# MCU.net
KiCad netlist of a schematic drawn in Altium Designer
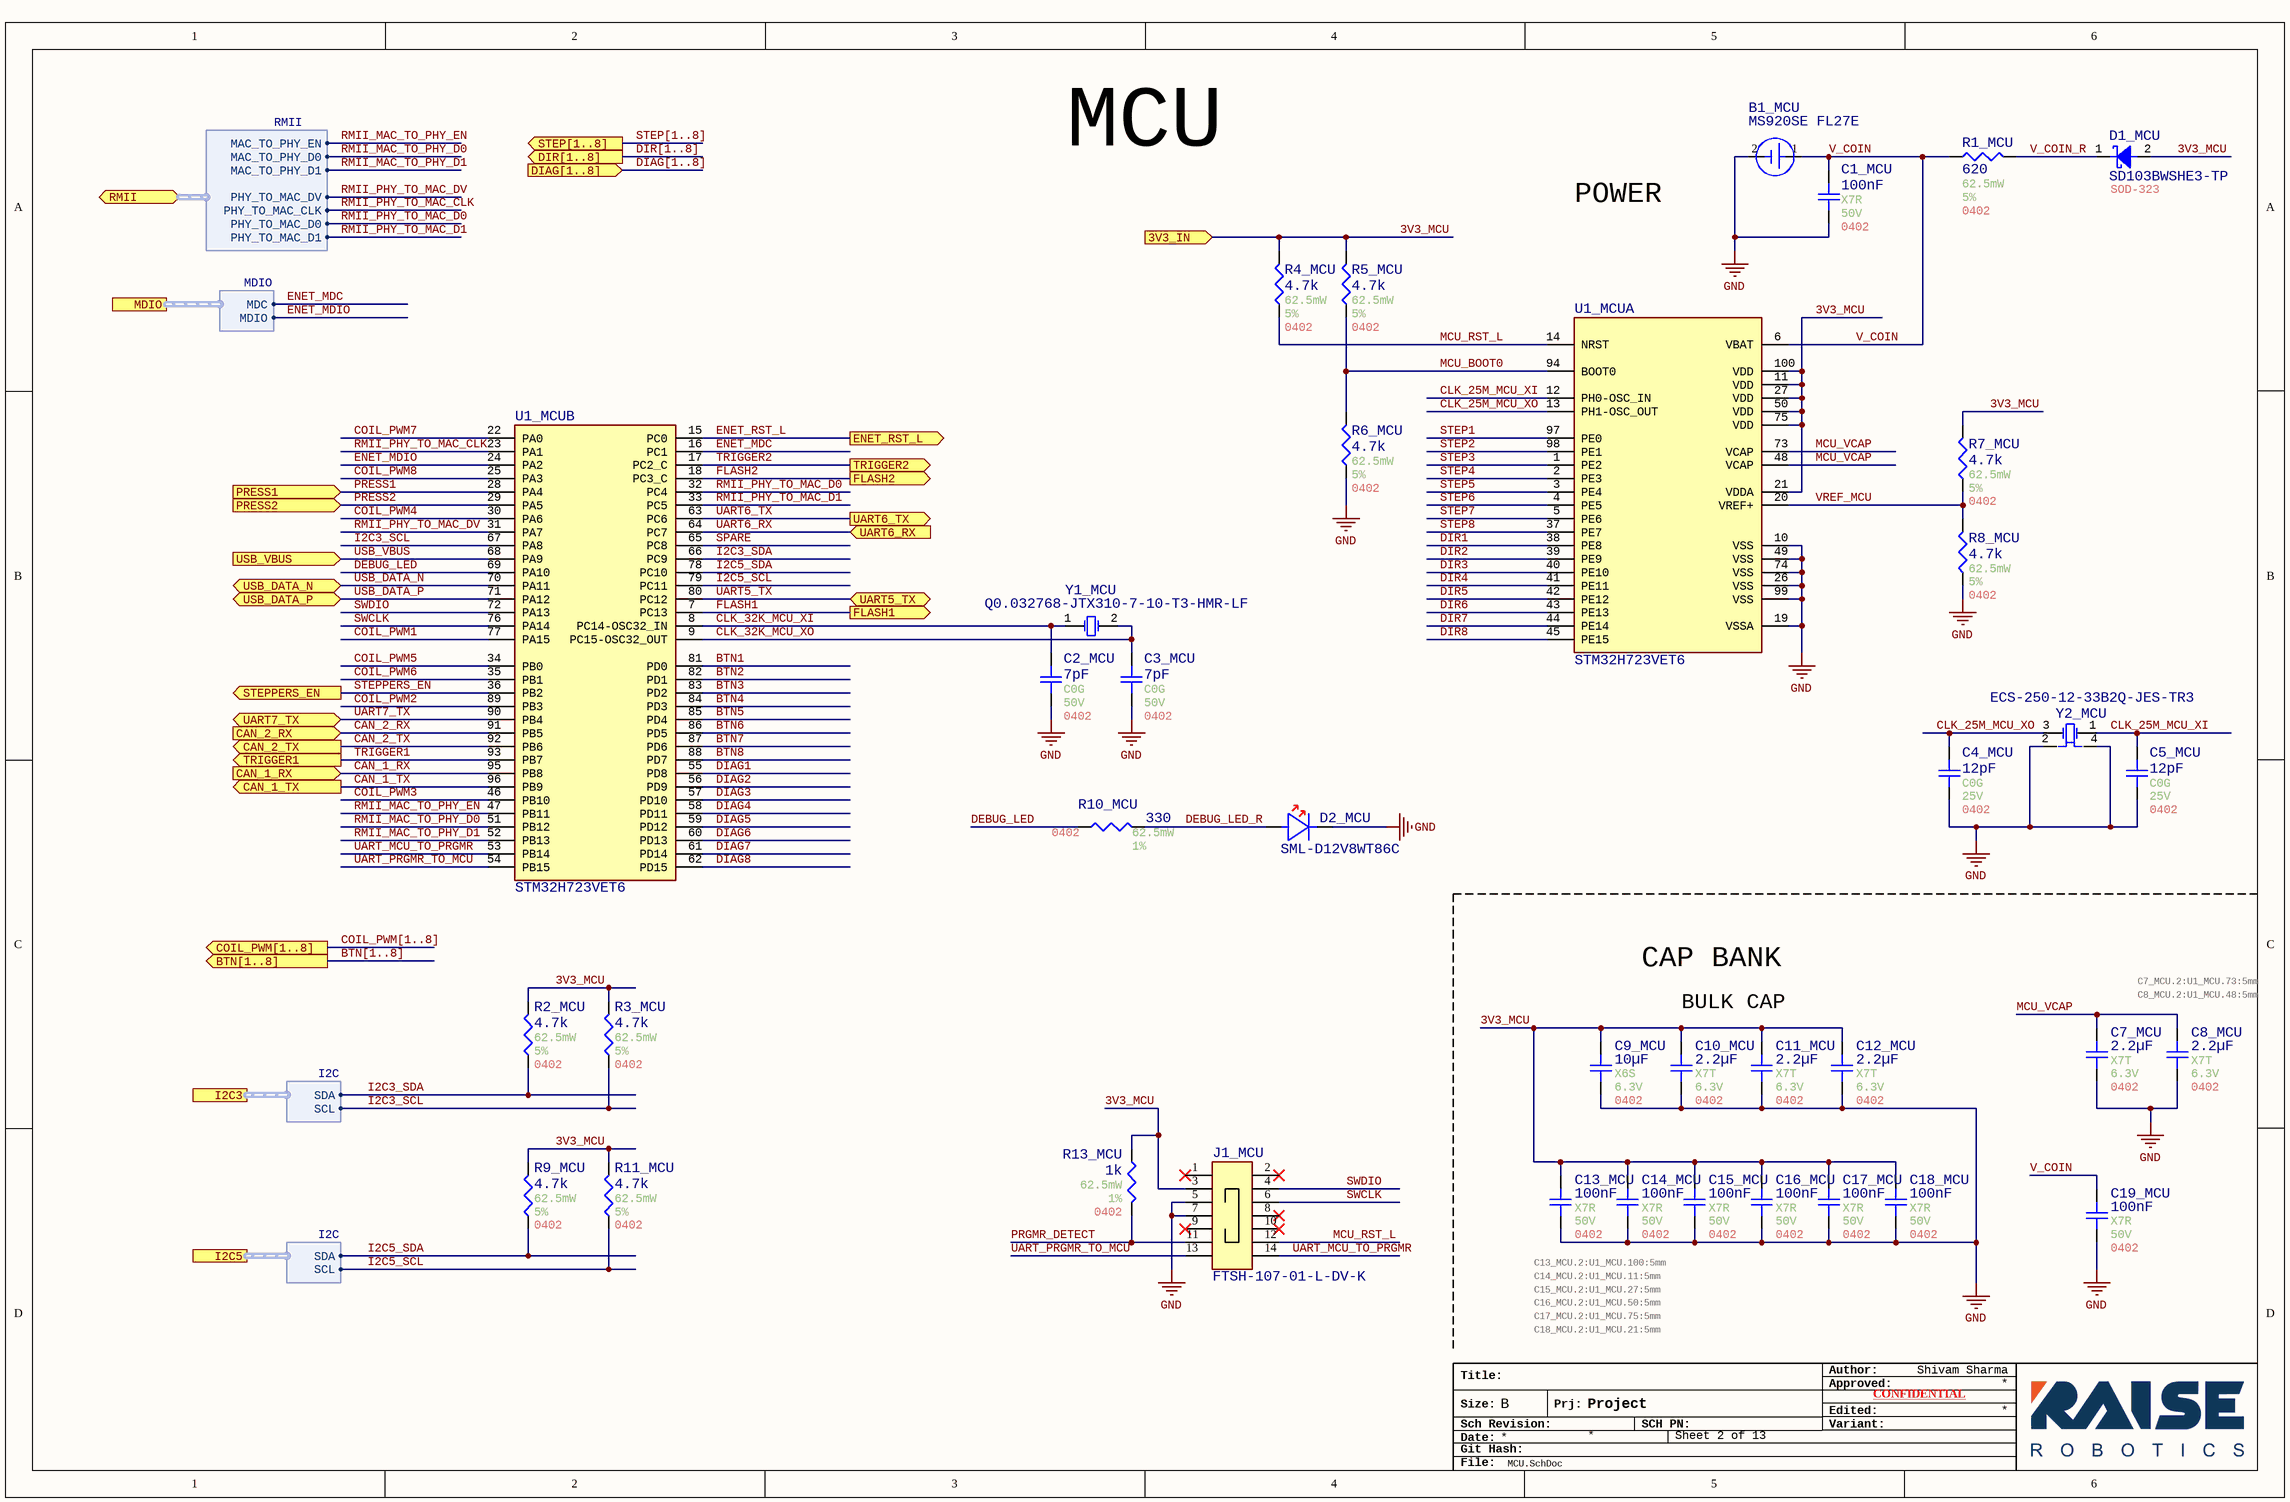
[diagram p0: MCU.SchDoc]

(export (version "E")
  (design (tool "Eeschema 10.0.6"))
  (components
    (comp (ref "B1_MCU")
      (value "MS920SE FL27E")
      (footprint "MS920SE-FL27E")
      (description "Secondary Battery, Manganese Silicon Lithium, 3V, 0.011Ah")
      (libsource (lib "Raise Robotics") (part "Coin Cell"))
    )
    (comp (ref "C1_MCU")
      (value "100nF")
      (footprint "Generic 0402 capacitor")
      (fields
        (field (name "TEMPERATURE COEFFICIENT") "X7R")
        (field (name "VOLTAGE RATING") "50V")
        (field (name "CASE/PACKAGE") "0402")
        (field (name "TOLERANCE") "10%")
        (field (name "Comment") "GRT155R71H104KE01D")
      )
      (libsource (lib "Raise Robotics") (part "Unpolarized Capacitor"))
    )
    (comp (ref "C2_MCU")
      (value "7pF")
      (footprint "Generic 0402 capacitor")
      (fields
        (field (name "TEMPERATURE COEFFICIENT") "C0G")
        (field (name "VOLTAGE RATING") "50V")
        (field (name "CASE/PACKAGE") "0402")
        (field (name "TOLERANCE") "3.5%")
        (field (name "Comment") "GCM1555C1H7R0CA16J")
      )
      (libsource (lib "Raise Robotics") (part "Unpolarized Capacitor"))
    )
    (comp (ref "C3_MCU")
      (value "7pF")
      (footprint "Generic 0402 capacitor")
      (fields
        (field (name "TEMPERATURE COEFFICIENT") "C0G")
        (field (name "VOLTAGE RATING") "50V")
        (field (name "CASE/PACKAGE") "0402")
        (field (name "TOLERANCE") "3.5%")
        (field (name "Comment") "GCM1555C1H7R0CA16J")
      )
      (libsource (lib "Raise Robotics") (part "Unpolarized Capacitor"))
    )
    (comp (ref "C4_MCU")
      (value "12pF")
      (footprint "Generic 0402 capacitor")
      (fields
        (field (name "TEMPERATURE COEFFICIENT") "C0G")
        (field (name "VOLTAGE RATING") "25V")
        (field (name "CASE/PACKAGE") "0402")
        (field (name "TOLERANCE") "5%")
        (field (name "Comment") "GRT1555C1E120JA02J")
      )
      (libsource (lib "Raise Robotics") (part "Unpolarized Capacitor"))
    )
    (comp (ref "C5_MCU")
      (value "12pF")
      (footprint "Generic 0402 capacitor")
      (fields
        (field (name "TEMPERATURE COEFFICIENT") "C0G")
        (field (name "VOLTAGE RATING") "25V")
        (field (name "CASE/PACKAGE") "0402")
        (field (name "TOLERANCE") "5%")
        (field (name "Comment") "GRT1555C1E120JA02J")
      )
      (libsource (lib "Raise Robotics") (part "Unpolarized Capacitor"))
    )
    (comp (ref "C7_MCU")
      (value "2.2µF")
      (footprint "Generic 0402 capacitor")
      (description "Mlcc, 2.2 Uf, # 20 %, 0402, 6.3V, X7T, T&r Q200")
      (fields
        (field (name "TEMPERATURE COEFFICIENT") "X7T")
        (field (name "VOLTAGE RATING") "6.3V")
        (field (name "CASE/PACKAGE") "0402")
        (field (name "TOLERANCE") "20%")
        (field (name "PLACENEAR") "C7_MCU.2:U1_MCU.73:5mm")
        (field (name "Comment") "MAASJ105CD7225MFCA01")
      )
      (libsource (lib "Raise Robotics") (part "Unpolarized Capacitor"))
    )
    (comp (ref "C8_MCU")
      (value "2.2µF")
      (footprint "Generic 0402 capacitor")
      (description "Mlcc, 2.2 Uf, # 20 %, 0402, 6.3V, X7T, T&r Q200")
      (fields
        (field (name "TEMPERATURE COEFFICIENT") "X7T")
        (field (name "VOLTAGE RATING") "6.3V")
        (field (name "CASE/PACKAGE") "0402")
        (field (name "TOLERANCE") "20%")
        (field (name "PLACENEAR") "C8_MCU.2:U1_MCU.48:5mm")
        (field (name "Comment") "MAASJ105CD7225MFCA01")
      )
      (libsource (lib "Raise Robotics") (part "Unpolarized Capacitor"))
    )
    (comp (ref "C9_MCU")
      (value "10µF")
      (footprint "Generic 0402 capacitor")
      (description "Multilayer Ceramic Capacitors MLCC - SMD/SMT 0402 10uF 6.3VDC 20% X6S AEC-Q200")
      (fields
        (field (name "TEMPERATURE COEFFICIENT") "X6S")
        (field (name "VOLTAGE RATING") "6.3V")
        (field (name "CASE/PACKAGE") "0402")
        (field (name "TOLERANCE") "20%")
        (field (name "Comment") "GRT155C80J106ME13J")
      )
      (libsource (lib "Raise Robotics") (part "Unpolarized Capacitor"))
    )
    (comp (ref "C10_MCU")
      (value "2.2µF")
      (footprint "Generic 0402 capacitor")
      (description "Mlcc, 2.2 Uf, # 20 %, 0402, 6.3V, X7T, T&r Q200")
      (fields
        (field (name "TEMPERATURE COEFFICIENT") "X7T")
        (field (name "VOLTAGE RATING") "6.3V")
        (field (name "CASE/PACKAGE") "0402")
        (field (name "TOLERANCE") "20%")
        (field (name "Comment") "MAASJ105CD7225MFCA01")
      )
      (libsource (lib "Raise Robotics") (part "Unpolarized Capacitor"))
    )
    (comp (ref "C11_MCU")
      (value "2.2µF")
      (footprint "Generic 0402 capacitor")
      (description "Mlcc, 2.2 Uf, # 20 %, 0402, 6.3V, X7T, T&r Q200")
      (fields
        (field (name "TEMPERATURE COEFFICIENT") "X7T")
        (field (name "VOLTAGE RATING") "6.3V")
        (field (name "CASE/PACKAGE") "0402")
        (field (name "TOLERANCE") "20%")
        (field (name "Comment") "MAASJ105CD7225MFCA01")
      )
      (libsource (lib "Raise Robotics") (part "Unpolarized Capacitor"))
    )
    (comp (ref "C12_MCU")
      (value "2.2µF")
      (footprint "Generic 0402 capacitor")
      (description "Mlcc, 2.2 Uf, # 20 %, 0402, 6.3V, X7T, T&r Q200")
      (fields
        (field (name "TEMPERATURE COEFFICIENT") "X7T")
        (field (name "VOLTAGE RATING") "6.3V")
        (field (name "CASE/PACKAGE") "0402")
        (field (name "TOLERANCE") "20%")
        (field (name "Comment") "MAASJ105CD7225MFCA01")
      )
      (libsource (lib "Raise Robotics") (part "Unpolarized Capacitor"))
    )
    (comp (ref "C13_MCU")
      (value "100nF")
      (footprint "Generic 0402 capacitor")
      (fields
        (field (name "TEMPERATURE COEFFICIENT") "X7R")
        (field (name "VOLTAGE RATING") "50V")
        (field (name "CASE/PACKAGE") "0402")
        (field (name "TOLERANCE") "10%")
        (field (name "PLACENEAR") "C13_MCU.2:U1_MCU.100:5mm")
        (field (name "Comment") "GRT155R71H104KE01D")
      )
      (libsource (lib "Raise Robotics") (part "Unpolarized Capacitor"))
    )
    (comp (ref "C14_MCU")
      (value "100nF")
      (footprint "Generic 0402 capacitor")
      (fields
        (field (name "TEMPERATURE COEFFICIENT") "X7R")
        (field (name "VOLTAGE RATING") "50V")
        (field (name "CASE/PACKAGE") "0402")
        (field (name "TOLERANCE") "10%")
        (field (name "PLACENEAR") "C14_MCU.2:U1_MCU.11:5mm")
        (field (name "Comment") "GRT155R71H104KE01D")
      )
      (libsource (lib "Raise Robotics") (part "Unpolarized Capacitor"))
    )
    (comp (ref "C15_MCU")
      (value "100nF")
      (footprint "Generic 0402 capacitor")
      (fields
        (field (name "TEMPERATURE COEFFICIENT") "X7R")
        (field (name "VOLTAGE RATING") "50V")
        (field (name "CASE/PACKAGE") "0402")
        (field (name "TOLERANCE") "10%")
        (field (name "PLACENEAR") "C15_MCU.2:U1_MCU.27:5mm")
        (field (name "Comment") "GRT155R71H104KE01D")
      )
      (libsource (lib "Raise Robotics") (part "Unpolarized Capacitor"))
    )
    (comp (ref "C16_MCU")
      (value "100nF")
      (footprint "Generic 0402 capacitor")
      (fields
        (field (name "TEMPERATURE COEFFICIENT") "X7R")
        (field (name "VOLTAGE RATING") "50V")
        (field (name "CASE/PACKAGE") "0402")
        (field (name "TOLERANCE") "10%")
        (field (name "PLACENEAR") "C16_MCU.2:U1_MCU.50:5mm")
        (field (name "Comment") "GRT155R71H104KE01D")
      )
      (libsource (lib "Raise Robotics") (part "Unpolarized Capacitor"))
    )
    (comp (ref "C17_MCU")
      (value "100nF")
      (footprint "Generic 0402 capacitor")
      (fields
        (field (name "TEMPERATURE COEFFICIENT") "X7R")
        (field (name "VOLTAGE RATING") "50V")
        (field (name "CASE/PACKAGE") "0402")
        (field (name "TOLERANCE") "10%")
        (field (name "PLACENEAR") "C17_MCU.2:U1_MCU.75:5mm")
        (field (name "Comment") "GRT155R71H104KE01D")
      )
      (libsource (lib "Raise Robotics") (part "Unpolarized Capacitor"))
    )
    (comp (ref "C18_MCU")
      (value "100nF")
      (footprint "Generic 0402 capacitor")
      (fields
        (field (name "TEMPERATURE COEFFICIENT") "X7R")
        (field (name "VOLTAGE RATING") "50V")
        (field (name "CASE/PACKAGE") "0402")
        (field (name "TOLERANCE") "10%")
        (field (name "PLACENEAR") "C18_MCU.2:U1_MCU.21:5mm")
        (field (name "Comment") "GRT155R71H104KE01D")
      )
      (libsource (lib "Raise Robotics") (part "Unpolarized Capacitor"))
    )
    (comp (ref "C19_MCU")
      (value "100nF")
      (footprint "Generic 0402 capacitor")
      (fields
        (field (name "TEMPERATURE COEFFICIENT") "X7R")
        (field (name "VOLTAGE RATING") "50V")
        (field (name "CASE/PACKAGE") "0402")
        (field (name "TOLERANCE") "10%")
        (field (name "Comment") "GRT155R71H104KE01D")
      )
      (libsource (lib "Raise Robotics") (part "Unpolarized Capacitor"))
    )
    (comp (ref "D1_MCU")
      (value "SD103BWSHE3-TP")
      (footprint "SOD-323")
      (description "Rectifier Diode, Schottky, 1 Phase, 1 Element, 0.35A, 30V V(RRM), Silicon")
      (fields (field (name "CASE/PACKAGE") "SOD-323"))
      (libsource (lib "Raise Robotics") (part "Generic 2 pin Diode"))
    )
    (comp (ref "D2_MCU")
      (value "SML-D12V8WT86C")
      (footprint "FP-SML-D12-MFG")
      (description "Red 630nm LED Indication - Discrete 2.2V 0603 (1608 Metric)")
      (libsource (lib "Raise Robotics") (part "LED Red"))
    )
    (comp (ref "J1_MCU")
      (value "FTSH-107-01-L-DV-K")
      (footprint "FTSH-107-01-L-DV-K-TR")
      (fields (field (name "MANUFACTURER") "Samtec"))
      (libsource (lib "Raise Robotics") (part "FTSH-107-01-L-DV-K-A"))
    )
    (comp (ref "R1_MCU")
      (value "620")
      (footprint "Generic 0402 Resistor")
      (fields
        (field (name "POWER") "62.5mW")
        (field (name "TOLERANCE") "5%")
        (field (name "CASE/PACKAGE") "0402")
        (field (name "Comment") "RC0402JR-07620RL")
      )
      (libsource (lib "Raise Robotics") (part "Resistor"))
    )
    (comp (ref "R2_MCU")
      (value "4.7k")
      (footprint "Generic 0402 Resistor")
      (fields
        (field (name "POWER") "62.5mW")
        (field (name "TOLERANCE") "5%")
        (field (name "CASE/PACKAGE") "0402")
        (field (name "MANUFACTURER PART NUMBER") "Blank")
        (field (name "Comment") "WR04X472JTL")
      )
      (libsource (lib "Raise Robotics") (part "Resistor"))
    )
    (comp (ref "R3_MCU")
      (value "4.7k")
      (footprint "Generic 0402 Resistor")
      (fields
        (field (name "POWER") "62.5mW")
        (field (name "TOLERANCE") "5%")
        (field (name "CASE/PACKAGE") "0402")
        (field (name "MANUFACTURER PART NUMBER") "Blank")
        (field (name "Comment") "WR04X472JTL")
      )
      (libsource (lib "Raise Robotics") (part "Resistor"))
    )
    (comp (ref "R4_MCU")
      (value "4.7k")
      (footprint "Generic 0402 Resistor")
      (fields
        (field (name "POWER") "62.5mW")
        (field (name "TOLERANCE") "5%")
        (field (name "CASE/PACKAGE") "0402")
        (field (name "MANUFACTURER PART NUMBER") "Blank")
        (field (name "Comment") "WR04X472JTL")
      )
      (libsource (lib "Raise Robotics") (part "Resistor"))
    )
    (comp (ref "R5_MCU")
      (value "4.7k")
      (footprint "Generic 0402 Resistor")
      (fields
        (field (name "POWER") "62.5mW")
        (field (name "TOLERANCE") "5%")
        (field (name "CASE/PACKAGE") "0402")
        (field (name "MANUFACTURER PART NUMBER") "Blank")
        (field (name "Comment") "WR04X472JTL")
      )
      (libsource (lib "Raise Robotics") (part "Resistor"))
    )
    (comp (ref "R6_MCU")
      (value "4.7k")
      (footprint "Generic 0402 Resistor")
      (fields
        (field (name "POWER") "62.5mW")
        (field (name "TOLERANCE") "5%")
        (field (name "CASE/PACKAGE") "0402")
        (field (name "MANUFACTURER PART NUMBER") "Blank")
        (field (name "Comment") "WR04X472JTL")
      )
      (libsource (lib "Raise Robotics") (part "Resistor"))
    )
    (comp (ref "R7_MCU")
      (value "4.7k")
      (footprint "Generic 0402 Resistor")
      (fields
        (field (name "POWER") "62.5mW")
        (field (name "TOLERANCE") "5%")
        (field (name "CASE/PACKAGE") "0402")
        (field (name "MANUFACTURER PART NUMBER") "Blank")
        (field (name "Comment") "WR04X472JTL")
      )
      (libsource (lib "Raise Robotics") (part "Resistor"))
    )
    (comp (ref "R8_MCU")
      (value "4.7k")
      (footprint "Generic 0402 Resistor")
      (fields
        (field (name "POWER") "62.5mW")
        (field (name "TOLERANCE") "5%")
        (field (name "CASE/PACKAGE") "0402")
        (field (name "MANUFACTURER PART NUMBER") "Blank")
        (field (name "Comment") "WR04X472JTL")
      )
      (libsource (lib "Raise Robotics") (part "Resistor"))
    )
    (comp (ref "R9_MCU")
      (value "4.7k")
      (footprint "Generic 0402 Resistor")
      (fields
        (field (name "POWER") "62.5mW")
        (field (name "TOLERANCE") "5%")
        (field (name "CASE/PACKAGE") "0402")
        (field (name "MANUFACTURER PART NUMBER") "Blank")
        (field (name "Comment") "WR04X472JTL")
      )
      (libsource (lib "Raise Robotics") (part "Resistor"))
    )
    (comp (ref "R10_MCU")
      (value "330")
      (footprint "Generic 0402 Resistor")
      (description "Res Thick Film 0402 330 Ohm 1% 0.063W ±100ppm/°C Molded SMD Paper T/R")
      (fields
        (field (name "POWER") "62.5mW")
        (field (name "TOLERANCE") "1%")
        (field (name "CASE/PACKAGE") "0402")
        (field (name "Comment") "RMCF0402FT330R")
      )
      (libsource (lib "Raise Robotics") (part "Resistor"))
    )
    (comp (ref "R11_MCU")
      (value "4.7k")
      (footprint "Generic 0402 Resistor")
      (fields
        (field (name "POWER") "62.5mW")
        (field (name "TOLERANCE") "5%")
        (field (name "CASE/PACKAGE") "0402")
        (field (name "MANUFACTURER PART NUMBER") "Blank")
        (field (name "Comment") "WR04X472JTL")
      )
      (libsource (lib "Raise Robotics") (part "Resistor"))
    )
    (comp (ref "R13_MCU")
      (value "1k")
      (footprint "Generic 0402 Resistor")
      (fields
        (field (name "POWER") "62.5mW")
        (field (name "TOLERANCE") "1%")
        (field (name "CASE/PACKAGE") "0402")
        (field (name "MANUFACTURER PART NUMBER") "Blank")
        (field (name "Comment") "WR04X1001FTL")
      )
      (libsource (lib "Raise Robotics") (part "Resistor"))
    )
    (comp (ref "U1_MCU")
      (value "STM32H723VET6")
      (footprint "STM32H723VxT")
      (description "MCU 32-bit ARM Cortex M7 RISC 512KB Flash 1.8V/2.5V/3.3V 100-Pin LQFP Tray")
      (libsource (lib "Raise Robotics") (part "STM32H723VET6"))
    )
    (comp (ref "Y1_MCU")
      (value "Q0.032768-JTX310-7-10-T3-HMR-LF")
      (footprint "JTX310")
      (description "Parallel - Fundamental Quartz Crystal, 0.032768MHz Nom")
      (libsource (lib "Raise Robotics") (part "XTAL-2"))
    )
    (comp (ref "Y2_MCU")
      (value "ECS-250-12-33B2Q-JES-TR3")
      (footprint "ECS-250-12-33B2Q-JES-TR3")
      (description "Crystal 25.000 Mhz 12PF SMD")
      (libsource (lib "") (part "XTAL-2_1"))
    )
  )
  (nets
    (net (code "4") (name "/3V3_MCU") (class "Default")
      (node (ref "C10_MCU") (pin "2") (pinfunction "2_2") (pintype "passive"))
      (node (ref "C11_MCU") (pin "2") (pinfunction "2_2") (pintype "passive"))
      (node (ref "C12_MCU") (pin "2") (pinfunction "2_2") (pintype "passive"))
      (node (ref "C13_MCU") (pin "2") (pinfunction "2_2") (pintype "passive"))
      (node (ref "C14_MCU") (pin "2") (pinfunction "2_2") (pintype "passive"))
      (node (ref "C15_MCU") (pin "2") (pinfunction "2_2") (pintype "passive"))
      (node (ref "C16_MCU") (pin "2") (pinfunction "2_2") (pintype "passive"))
      (node (ref "C17_MCU") (pin "2") (pinfunction "2_2") (pintype "passive"))
      (node (ref "C18_MCU") (pin "2") (pinfunction "2_2") (pintype "passive"))
      (node (ref "C9_MCU") (pin "2") (pinfunction "2_2") (pintype "passive"))
      (node (ref "D1_MCU") (pin "2") (pinfunction "A_2") (pintype "passive"))
      (node (ref "J1_MCU") (pin "3") (pinfunction "3_3") (pintype "passive"))
      (node (ref "R11_MCU") (pin "2") (pinfunction "2_2") (pintype "passive"))
      (node (ref "R13_MCU") (pin "2") (pinfunction "2_2") (pintype "passive"))
      (node (ref "R2_MCU") (pin "2") (pinfunction "2_2") (pintype "passive"))
      (node (ref "R3_MCU") (pin "2") (pinfunction "2_2") (pintype "passive"))
      (node (ref "R4_MCU") (pin "2") (pinfunction "2_2") (pintype "passive"))
      (node (ref "R5_MCU") (pin "2") (pinfunction "2_2") (pintype "passive"))
      (node (ref "R7_MCU") (pin "2") (pinfunction "2_2") (pintype "passive"))
      (node (ref "R9_MCU") (pin "2") (pinfunction "2_2") (pintype "passive"))
      (node (ref "U1_MCU") (pin "100") (pinfunction "VDD_100") (pintype "passive"))
      (node (ref "U1_MCU") (pin "11") (pinfunction "VDD_11") (pintype "passive"))
      (node (ref "U1_MCU") (pin "21") (pinfunction "VDDA_21") (pintype "passive"))
      (node (ref "U1_MCU") (pin "27") (pinfunction "VDD_27") (pintype "passive"))
      (node (ref "U1_MCU") (pin "50") (pinfunction "VDD_50") (pintype "passive"))
      (node (ref "U1_MCU") (pin "75") (pinfunction "VDD_75") (pintype "passive"))
    )
    (net (code "5") (name "/BTN1") (class "Default")
      (node (ref "U1_MCU") (pin "81") (pinfunction "PD0_81") (pintype "passive"))
    )
    (net (code "6") (name "/BTN2") (class "Default")
      (node (ref "U1_MCU") (pin "82") (pinfunction "PD1_82") (pintype "passive"))
    )
    (net (code "7") (name "/BTN3") (class "Default")
      (node (ref "U1_MCU") (pin "83") (pinfunction "PD2_83") (pintype "passive"))
    )
    (net (code "8") (name "/BTN4") (class "Default")
      (node (ref "U1_MCU") (pin "84") (pinfunction "PD3_84") (pintype "passive"))
    )
    (net (code "9") (name "/BTN5") (class "Default")
      (node (ref "U1_MCU") (pin "85") (pinfunction "PD4_85") (pintype "passive"))
    )
    (net (code "10") (name "/BTN6") (class "Default")
      (node (ref "U1_MCU") (pin "86") (pinfunction "PD5_86") (pintype "passive"))
    )
    (net (code "11") (name "/BTN7") (class "Default")
      (node (ref "U1_MCU") (pin "87") (pinfunction "PD6_87") (pintype "passive"))
    )
    (net (code "12") (name "/BTN8") (class "Default")
      (node (ref "U1_MCU") (pin "88") (pinfunction "PD7_88") (pintype "passive"))
    )
    (net (code "14") (name "/CAN_1_RX") (class "Default")
      (node (ref "U1_MCU") (pin "95") (pinfunction "PB8_95") (pintype "passive"))
    )
    (net (code "15") (name "/CAN_1_TX") (class "Default")
      (node (ref "U1_MCU") (pin "96") (pinfunction "PB9_96") (pintype "passive"))
    )
    (net (code "16") (name "/CAN_2_RX") (class "Default")
      (node (ref "U1_MCU") (pin "91") (pinfunction "PB5_91") (pintype "passive"))
    )
    (net (code "17") (name "/CAN_2_TX") (class "Default")
      (node (ref "U1_MCU") (pin "92") (pinfunction "PB6_92") (pintype "passive"))
    )
    (net (code "18") (name "/CLK_25M_MCU_XI") (class "Default")
      (node (ref "C5_MCU") (pin "2") (pinfunction "2_2") (pintype "passive"))
      (node (ref "U1_MCU") (pin "12") (pinfunction "PH0-OSC_IN_12") (pintype "passive"))
      (node (ref "Y2_MCU") (pin "1") (pinfunction "1_1") (pintype "passive"))
    )
    (net (code "19") (name "/CLK_25M_MCU_XO") (class "Default")
      (node (ref "C4_MCU") (pin "2") (pinfunction "2_2") (pintype "passive"))
      (node (ref "U1_MCU") (pin "13") (pinfunction "PH1-OSC_OUT_13") (pintype "passive"))
      (node (ref "Y2_MCU") (pin "3") (pinfunction "3_3") (pintype "passive"))
    )
    (net (code "20") (name "/CLK_32K_MCU_XI") (class "Default")
      (node (ref "C2_MCU") (pin "2") (pinfunction "2_2") (pintype "passive"))
      (node (ref "U1_MCU") (pin "8") (pinfunction "PC14-OSC32_IN_8") (pintype "passive"))
      (node (ref "Y1_MCU") (pin "1") (pinfunction "1_1") (pintype "passive"))
    )
    (net (code "21") (name "/CLK_32K_MCU_XO") (class "Default")
      (node (ref "C3_MCU") (pin "2") (pinfunction "2_2") (pintype "passive"))
      (node (ref "U1_MCU") (pin "9") (pinfunction "PC15-OSC32_OUT_9") (pintype "passive"))
      (node (ref "Y1_MCU") (pin "2") (pinfunction "2_2") (pintype "passive"))
    )
    (net (code "22") (name "/COIL_PWM1") (class "Default")
      (node (ref "U1_MCU") (pin "77") (pinfunction "PA15_77") (pintype "passive"))
    )
    (net (code "23") (name "/COIL_PWM2") (class "Default")
      (node (ref "U1_MCU") (pin "89") (pinfunction "PB3_89") (pintype "passive"))
    )
    (net (code "24") (name "/COIL_PWM3") (class "Default")
      (node (ref "U1_MCU") (pin "46") (pinfunction "PB10_46") (pintype "passive"))
    )
    (net (code "25") (name "/COIL_PWM4") (class "Default")
      (node (ref "U1_MCU") (pin "30") (pinfunction "PA6_30") (pintype "passive"))
    )
    (net (code "26") (name "/COIL_PWM5") (class "Default")
      (node (ref "U1_MCU") (pin "34") (pinfunction "PB0_34") (pintype "passive"))
    )
    (net (code "27") (name "/COIL_PWM6") (class "Default")
      (node (ref "U1_MCU") (pin "35") (pinfunction "PB1_35") (pintype "passive"))
    )
    (net (code "28") (name "/COIL_PWM7") (class "Default")
      (node (ref "U1_MCU") (pin "22") (pinfunction "PA0_22") (pintype "passive"))
    )
    (net (code "29") (name "/COIL_PWM8") (class "Default")
      (node (ref "U1_MCU") (pin "25") (pinfunction "PA3_25") (pintype "passive"))
    )
    (net (code "31") (name "/DEBUG_LED") (class "Default")
      (node (ref "R10_MCU") (pin "1") (pinfunction "1_1") (pintype "passive"))
      (node (ref "U1_MCU") (pin "69") (pinfunction "PA10_69") (pintype "passive"))
    )
    (net (code "32") (name "/DEBUG_LED_R") (class "Default")
      (node (ref "D2_MCU") (pin "2") (pinfunction "A_2") (pintype "passive"))
      (node (ref "R10_MCU") (pin "2") (pinfunction "2_2") (pintype "passive"))
    )
    (net (code "33") (name "/DIAG1") (class "Default")
      (node (ref "U1_MCU") (pin "55") (pinfunction "PD8_55") (pintype "passive"))
    )
    (net (code "34") (name "/DIAG2") (class "Default")
      (node (ref "U1_MCU") (pin "56") (pinfunction "PD9_56") (pintype "passive"))
    )
    (net (code "35") (name "/DIAG3") (class "Default")
      (node (ref "U1_MCU") (pin "57") (pinfunction "PD10_57") (pintype "passive"))
    )
    (net (code "36") (name "/DIAG4") (class "Default")
      (node (ref "U1_MCU") (pin "58") (pinfunction "PD11_58") (pintype "passive"))
    )
    (net (code "37") (name "/DIAG5") (class "Default")
      (node (ref "U1_MCU") (pin "59") (pinfunction "PD12_59") (pintype "passive"))
    )
    (net (code "38") (name "/DIAG6") (class "Default")
      (node (ref "U1_MCU") (pin "60") (pinfunction "PD13_60") (pintype "passive"))
    )
    (net (code "39") (name "/DIAG7") (class "Default")
      (node (ref "U1_MCU") (pin "61") (pinfunction "PD14_61") (pintype "passive"))
    )
    (net (code "40") (name "/DIAG8") (class "Default")
      (node (ref "U1_MCU") (pin "62") (pinfunction "PD15_62") (pintype "passive"))
    )
    (net (code "42") (name "/DIR1") (class "Default")
      (node (ref "U1_MCU") (pin "38") (pinfunction "PE8_38") (pintype "passive"))
    )
    (net (code "43") (name "/DIR2") (class "Default")
      (node (ref "U1_MCU") (pin "39") (pinfunction "PE9_39") (pintype "passive"))
    )
    (net (code "44") (name "/DIR3") (class "Default")
      (node (ref "U1_MCU") (pin "40") (pinfunction "PE10_40") (pintype "passive"))
    )
    (net (code "45") (name "/DIR4") (class "Default")
      (node (ref "U1_MCU") (pin "41") (pinfunction "PE11_41") (pintype "passive"))
    )
    (net (code "46") (name "/DIR5") (class "Default")
      (node (ref "U1_MCU") (pin "42") (pinfunction "PE12_42") (pintype "passive"))
    )
    (net (code "47") (name "/DIR6") (class "Default")
      (node (ref "U1_MCU") (pin "43") (pinfunction "PE13_43") (pintype "passive"))
    )
    (net (code "48") (name "/DIR7") (class "Default")
      (node (ref "U1_MCU") (pin "44") (pinfunction "PE14_44") (pintype "passive"))
    )
    (net (code "49") (name "/DIR8") (class "Default")
      (node (ref "U1_MCU") (pin "45") (pinfunction "PE15_45") (pintype "passive"))
    )
    (net (code "51") (name "/ENET_MDC") (class "Default")
      (node (ref "U1_MCU") (pin "16") (pinfunction "PC1_16") (pintype "passive"))
    )
    (net (code "52") (name "/ENET_MDIO") (class "Default")
      (node (ref "U1_MCU") (pin "24") (pinfunction "PA2_24") (pintype "passive"))
    )
    (net (code "53") (name "/ENET_RST_L") (class "Default")
      (node (ref "U1_MCU") (pin "15") (pinfunction "PC0_15") (pintype "passive"))
    )
    (net (code "54") (name "/FLASH1") (class "Default")
      (node (ref "U1_MCU") (pin "7") (pinfunction "PC13_7") (pintype "passive"))
    )
    (net (code "55") (name "/FLASH2") (class "Default")
      (node (ref "U1_MCU") (pin "18") (pinfunction "PC3_C_18") (pintype "passive"))
    )
    (net (code "56") (name "/I2C3_SCL") (class "Default")
      (node (ref "R3_MCU") (pin "1") (pinfunction "1_1") (pintype "passive"))
      (node (ref "U1_MCU") (pin "67") (pinfunction "PA8_67") (pintype "passive"))
    )
    (net (code "57") (name "/I2C3_SDA") (class "Default")
      (node (ref "R2_MCU") (pin "1") (pinfunction "1_1") (pintype "passive"))
      (node (ref "U1_MCU") (pin "66") (pinfunction "PC9_66") (pintype "passive"))
    )
    (net (code "58") (name "/I2C5_SCL") (class "Default")
      (node (ref "R11_MCU") (pin "1") (pinfunction "1_1") (pintype "passive"))
      (node (ref "U1_MCU") (pin "79") (pinfunction "PC11_79") (pintype "passive"))
    )
    (net (code "59") (name "/I2C5_SDA") (class "Default")
      (node (ref "R9_MCU") (pin "1") (pinfunction "1_1") (pintype "passive"))
      (node (ref "U1_MCU") (pin "78") (pinfunction "PC10_78") (pintype "passive"))
    )
    (net (code "60") (name "/MCU_BOOT0") (class "Default")
      (node (ref "R5_MCU") (pin "1") (pinfunction "1_1") (pintype "passive"))
      (node (ref "R6_MCU") (pin "2") (pinfunction "2_2") (pintype "passive"))
      (node (ref "U1_MCU") (pin "94") (pinfunction "BOOT0_94") (pintype "passive"))
    )
    (net (code "61") (name "/MCU_RST_L") (class "Default")
      (node (ref "J1_MCU") (pin "12") (pinfunction "12_12") (pintype "passive"))
      (node (ref "R4_MCU") (pin "1") (pinfunction "1_1") (pintype "passive"))
      (node (ref "U1_MCU") (pin "14") (pinfunction "NRST_14") (pintype "passive"))
    )
    (net (code "62") (name "/MCU_VCAP") (class "Default")
      (node (ref "C7_MCU") (pin "2") (pinfunction "2_2") (pintype "passive"))
      (node (ref "C8_MCU") (pin "2") (pinfunction "2_2") (pintype "passive"))
      (node (ref "U1_MCU") (pin "48") (pinfunction "VCAP_48") (pintype "passive"))
      (node (ref "U1_MCU") (pin "73") (pinfunction "VCAP_73") (pintype "passive"))
    )
    (net (code "63") (name "/PRESS1") (class "Default")
      (node (ref "U1_MCU") (pin "28") (pinfunction "PA4_28") (pintype "passive"))
    )
    (net (code "64") (name "/PRESS2") (class "Default")
      (node (ref "U1_MCU") (pin "29") (pinfunction "PA5_29") (pintype "passive"))
    )
    (net (code "65") (name "/PRGMR_DETECT") (class "Default")
      (node (ref "J1_MCU") (pin "11") (pinfunction "11_11") (pintype "passive"))
      (node (ref "R13_MCU") (pin "1") (pinfunction "1_1") (pintype "passive"))
    )
    (net (code "66") (name "/RMII_MAC_TO_PHY_D0") (class "Default")
      (node (ref "U1_MCU") (pin "51") (pinfunction "PB12_51") (pintype "passive"))
    )
    (net (code "67") (name "/RMII_MAC_TO_PHY_D1") (class "Default")
      (node (ref "U1_MCU") (pin "52") (pinfunction "PB13_52") (pintype "passive"))
    )
    (net (code "68") (name "/RMII_MAC_TO_PHY_EN") (class "Default")
      (node (ref "U1_MCU") (pin "47") (pinfunction "PB11_47") (pintype "passive"))
    )
    (net (code "69") (name "/RMII_PHY_TO_MAC_CLK") (class "Default")
      (node (ref "U1_MCU") (pin "23") (pinfunction "PA1_23") (pintype "passive"))
    )
    (net (code "70") (name "/RMII_PHY_TO_MAC_D0") (class "Default")
      (node (ref "U1_MCU") (pin "32") (pinfunction "PC4_32") (pintype "passive"))
    )
    (net (code "71") (name "/RMII_PHY_TO_MAC_D1") (class "Default")
      (node (ref "U1_MCU") (pin "33") (pinfunction "PC5_33") (pintype "passive"))
    )
    (net (code "72") (name "/RMII_PHY_TO_MAC_DV") (class "Default")
      (node (ref "U1_MCU") (pin "31") (pinfunction "PA7_31") (pintype "passive"))
    )
    (net (code "73") (name "/SPARE") (class "Default")
      (node (ref "U1_MCU") (pin "65") (pinfunction "PC8_65") (pintype "passive"))
    )
    (net (code "74") (name "/STEP1") (class "Default")
      (node (ref "U1_MCU") (pin "97") (pinfunction "PE0_97") (pintype "passive"))
    )
    (net (code "75") (name "/STEP2") (class "Default")
      (node (ref "U1_MCU") (pin "98") (pinfunction "PE1_98") (pintype "passive"))
    )
    (net (code "76") (name "/STEP3") (class "Default")
      (node (ref "U1_MCU") (pin "1") (pinfunction "PE2_1") (pintype "passive"))
    )
    (net (code "77") (name "/STEP4") (class "Default")
      (node (ref "U1_MCU") (pin "2") (pinfunction "PE3_2") (pintype "passive"))
    )
    (net (code "78") (name "/STEP5") (class "Default")
      (node (ref "U1_MCU") (pin "3") (pinfunction "PE4_3") (pintype "passive"))
    )
    (net (code "79") (name "/STEP6") (class "Default")
      (node (ref "U1_MCU") (pin "4") (pinfunction "PE5_4") (pintype "passive"))
    )
    (net (code "80") (name "/STEP7") (class "Default")
      (node (ref "U1_MCU") (pin "5") (pinfunction "PE6_5") (pintype "passive"))
    )
    (net (code "81") (name "/STEP8") (class "Default")
      (node (ref "U1_MCU") (pin "37") (pinfunction "PE7_37") (pintype "passive"))
    )
    (net (code "82") (name "/STEPPERS_EN") (class "Default")
      (node (ref "U1_MCU") (pin "36") (pinfunction "PB2_36") (pintype "passive"))
    )
    (net (code "84") (name "/SWCLK") (class "Default")
      (node (ref "J1_MCU") (pin "6") (pinfunction "6_6") (pintype "passive"))
      (node (ref "U1_MCU") (pin "76") (pinfunction "PA14_76") (pintype "passive"))
    )
    (net (code "85") (name "/SWDIO") (class "Default")
      (node (ref "J1_MCU") (pin "4") (pinfunction "4_4") (pintype "passive"))
      (node (ref "U1_MCU") (pin "72") (pinfunction "PA13_72") (pintype "passive"))
    )
    (net (code "86") (name "/TRIGGER1") (class "Default")
      (node (ref "U1_MCU") (pin "93") (pinfunction "PB7_93") (pintype "passive"))
    )
    (net (code "87") (name "/TRIGGER2") (class "Default")
      (node (ref "U1_MCU") (pin "17") (pinfunction "PC2_C_17") (pintype "passive"))
    )
    (net (code "88") (name "/UART5_TX") (class "Default")
      (node (ref "U1_MCU") (pin "80") (pinfunction "PC12_80") (pintype "passive"))
    )
    (net (code "89") (name "/UART6_RX") (class "Default")
      (node (ref "U1_MCU") (pin "64") (pinfunction "PC7_64") (pintype "passive"))
    )
    (net (code "90") (name "/UART6_TX") (class "Default")
      (node (ref "U1_MCU") (pin "63") (pinfunction "PC6_63") (pintype "passive"))
    )
    (net (code "91") (name "/UART7_TX") (class "Default")
      (node (ref "U1_MCU") (pin "90") (pinfunction "PB4_90") (pintype "passive"))
    )
    (net (code "92") (name "/UART_MCU_TO_PRGMR") (class "Default")
      (node (ref "J1_MCU") (pin "14") (pinfunction "14_14") (pintype "passive"))
      (node (ref "U1_MCU") (pin "53") (pinfunction "PB14_53") (pintype "passive"))
    )
    (net (code "93") (name "/UART_PRGMR_TO_MCU") (class "Default")
      (node (ref "J1_MCU") (pin "13") (pinfunction "13_13") (pintype "passive"))
      (node (ref "U1_MCU") (pin "54") (pinfunction "PB15_54") (pintype "passive"))
    )
    (net (code "94") (name "/USB_DATA_N") (class "Default")
      (node (ref "U1_MCU") (pin "70") (pinfunction "PA11_70") (pintype "passive"))
    )
    (net (code "95") (name "/USB_DATA_P") (class "Default")
      (node (ref "U1_MCU") (pin "71") (pinfunction "PA12_71") (pintype "passive"))
    )
    (net (code "96") (name "/USB_VBUS") (class "Default")
      (node (ref "U1_MCU") (pin "68") (pinfunction "PA9_68") (pintype "passive"))
    )
    (net (code "97") (name "/VREF_MCU") (class "Default")
      (node (ref "R7_MCU") (pin "1") (pinfunction "1_1") (pintype "passive"))
      (node (ref "R8_MCU") (pin "2") (pinfunction "2_2") (pintype "passive"))
      (node (ref "U1_MCU") (pin "20") (pinfunction "VREF+_20") (pintype "passive"))
    )
    (net (code "98") (name "/V_COIN") (class "Default")
      (node (ref "B1_MCU") (pin "1") (pinfunction "1_1") (pintype "passive"))
      (node (ref "C19_MCU") (pin "2") (pinfunction "2_2") (pintype "passive"))
      (node (ref "C1_MCU") (pin "2") (pinfunction "2_2") (pintype "passive"))
      (node (ref "R1_MCU") (pin "1") (pinfunction "1_1") (pintype "passive"))
      (node (ref "U1_MCU") (pin "6") (pinfunction "VBAT_6") (pintype "passive"))
    )
    (net (code "99") (name "/V_COIN_R") (class "Default")
      (node (ref "D1_MCU") (pin "1") (pinfunction "C_1") (pintype "passive"))
      (node (ref "R1_MCU") (pin "2") (pinfunction "2_2") (pintype "passive"))
    )
    (net (code "103") (name "GND") (class "Default")
      (node (ref "B1_MCU") (pin "2") (pinfunction "2_2") (pintype "passive"))
      (node (ref "C10_MCU") (pin "1") (pinfunction "1_1") (pintype "passive"))
      (node (ref "C11_MCU") (pin "1") (pinfunction "1_1") (pintype "passive"))
      (node (ref "C12_MCU") (pin "1") (pinfunction "1_1") (pintype "passive"))
      (node (ref "C13_MCU") (pin "1") (pinfunction "1_1") (pintype "passive"))
      (node (ref "C14_MCU") (pin "1") (pinfunction "1_1") (pintype "passive"))
      (node (ref "C15_MCU") (pin "1") (pinfunction "1_1") (pintype "passive"))
      (node (ref "C16_MCU") (pin "1") (pinfunction "1_1") (pintype "passive"))
      (node (ref "C17_MCU") (pin "1") (pinfunction "1_1") (pintype "passive"))
      (node (ref "C18_MCU") (pin "1") (pinfunction "1_1") (pintype "passive"))
      (node (ref "C19_MCU") (pin "1") (pinfunction "1_1") (pintype "passive"))
      (node (ref "C1_MCU") (pin "1") (pinfunction "1_1") (pintype "passive"))
      (node (ref "C2_MCU") (pin "1") (pinfunction "1_1") (pintype "passive"))
      (node (ref "C3_MCU") (pin "1") (pinfunction "1_1") (pintype "passive"))
      (node (ref "C4_MCU") (pin "1") (pinfunction "1_1") (pintype "passive"))
      (node (ref "C5_MCU") (pin "1") (pinfunction "1_1") (pintype "passive"))
      (node (ref "C7_MCU") (pin "1") (pinfunction "1_1") (pintype "passive"))
      (node (ref "C8_MCU") (pin "1") (pinfunction "1_1") (pintype "passive"))
      (node (ref "C9_MCU") (pin "1") (pinfunction "1_1") (pintype "passive"))
      (node (ref "D2_MCU") (pin "1") (pinfunction "C_1") (pintype "passive"))
      (node (ref "J1_MCU") (pin "5") (pinfunction "5_5") (pintype "passive"))
      (node (ref "J1_MCU") (pin "7") (pinfunction "7_7") (pintype "passive"))
      (node (ref "R6_MCU") (pin "1") (pinfunction "1_1") (pintype "passive"))
      (node (ref "R8_MCU") (pin "1") (pinfunction "1_1") (pintype "passive"))
      (node (ref "U1_MCU") (pin "10") (pinfunction "VSS_10") (pintype "passive"))
      (node (ref "U1_MCU") (pin "19") (pinfunction "VSSA_19") (pintype "passive"))
      (node (ref "U1_MCU") (pin "26") (pinfunction "VSS_26") (pintype "passive"))
      (node (ref "U1_MCU") (pin "49") (pinfunction "VSS_49") (pintype "passive"))
      (node (ref "U1_MCU") (pin "74") (pinfunction "VSS_74") (pintype "passive"))
      (node (ref "U1_MCU") (pin "99") (pinfunction "VSS_99") (pintype "passive"))
      (node (ref "Y2_MCU") (pin "2") (pinfunction "2_2") (pintype "passive"))
      (node (ref "Y2_MCU") (pin "4") (pinfunction "4_4") (pintype "passive"))
    )
    (net (code "104") (name "unconnected-(J1_MCU-Pad1)") (class "Default")
      (node (ref "J1_MCU") (pin "1") (pinfunction "1_1") (pintype "passive+no_connect"))
    )
    (net (code "105") (name "unconnected-(J1_MCU-Pad2)") (class "Default")
      (node (ref "J1_MCU") (pin "2") (pinfunction "2_2") (pintype "passive+no_connect"))
    )
    (net (code "106") (name "unconnected-(J1_MCU-Pad8)") (class "Default")
      (node (ref "J1_MCU") (pin "8") (pinfunction "8_8") (pintype "passive+no_connect"))
    )
    (net (code "107") (name "unconnected-(J1_MCU-Pad9)") (class "Default")
      (node (ref "J1_MCU") (pin "9") (pinfunction "9_9") (pintype "passive+no_connect"))
    )
    (net (code "108") (name "unconnected-(J1_MCU-Pad10)") (class "Default")
      (node (ref "J1_MCU") (pin "10") (pinfunction "10_10") (pintype "passive+no_connect"))
    )
  )
)
